# fpga23-serdes-power.net
KiCad netlist of a schematic drawn in Altium Designer
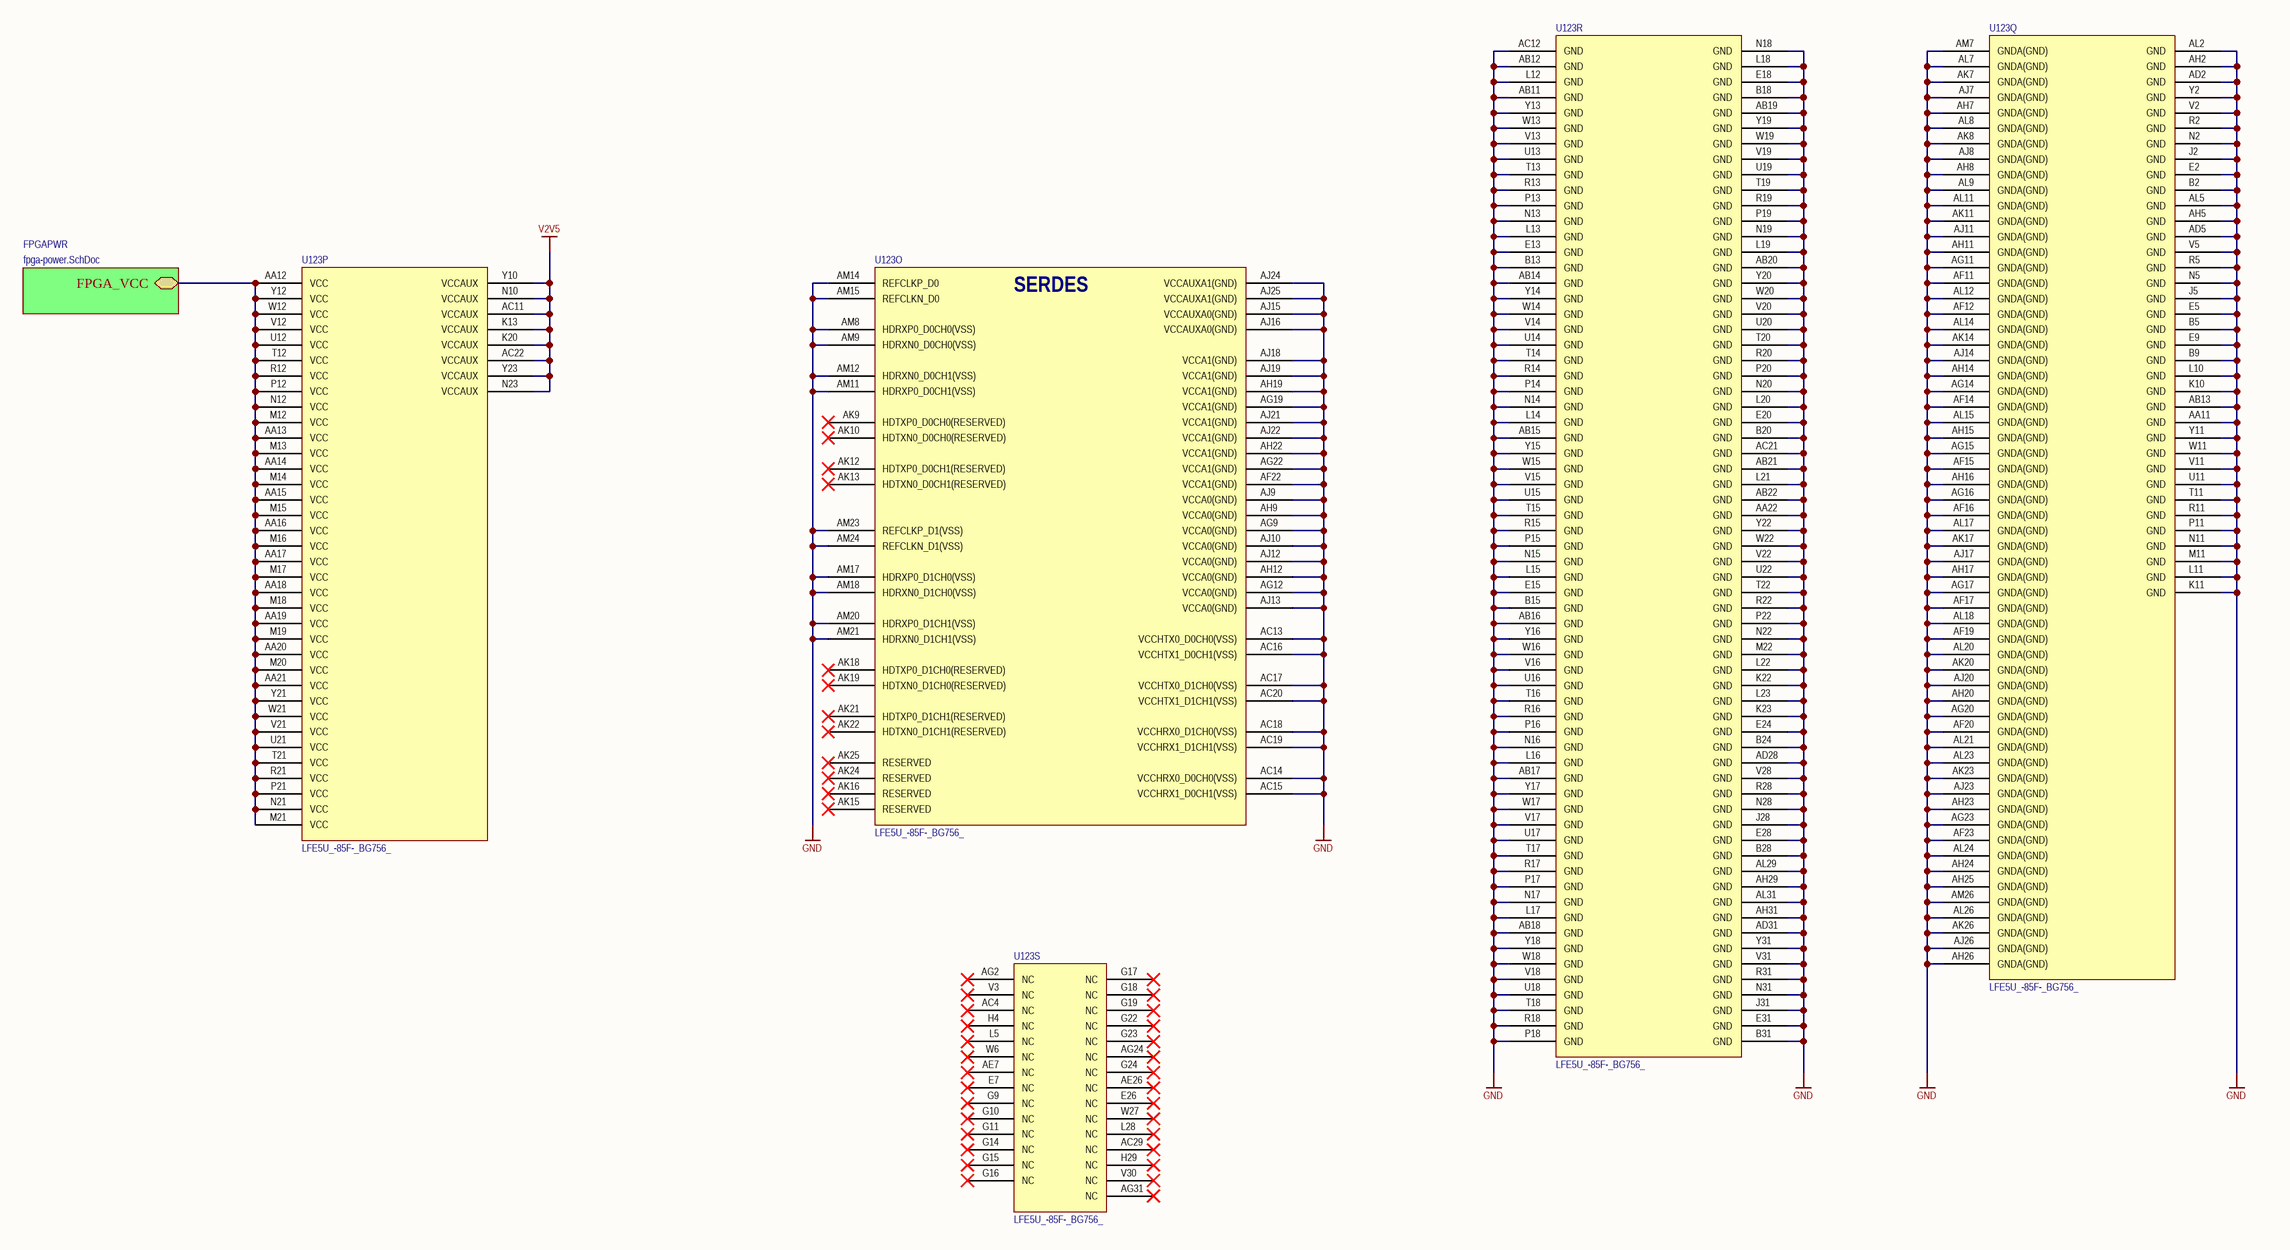
[diagram p0: fpga23-serdes-power.SchDoc]

(export (version "E")
  (design (tool "Eeschema 10.0.6"))
  (components
    (comp (ref "U123")
      (value "LFE5U_-85F-_BG756_")
      (footprint "lattice:caBGA756")
      (description "ECP5 FPGA, 85k LUT, 756-caBGA")
      (fields (field (name "MANUFACTURER") "Lattice Semiconductor"))
      (libsource (lib "lattice") (part "LFE5U_-85F-_BG756_"))
    )
  )
  (nets
    (net (code "1") (name "/FPGA_VCC") (class "Default")
      (node (ref "U123") (pin "AA12") (pinfunction "VCC_AA12") (pintype "power_in"))
      (node (ref "U123") (pin "AA13") (pinfunction "VCC_AA13") (pintype "power_in"))
      (node (ref "U123") (pin "AA14") (pinfunction "VCC_AA14") (pintype "power_in"))
      (node (ref "U123") (pin "AA15") (pinfunction "VCC_AA15") (pintype "power_in"))
      (node (ref "U123") (pin "AA16") (pinfunction "VCC_AA16") (pintype "power_in"))
      (node (ref "U123") (pin "AA17") (pinfunction "VCC_AA17") (pintype "power_in"))
      (node (ref "U123") (pin "AA18") (pinfunction "VCC_AA18") (pintype "power_in"))
      (node (ref "U123") (pin "AA19") (pinfunction "VCC_AA19") (pintype "power_in"))
      (node (ref "U123") (pin "AA20") (pinfunction "VCC_AA20") (pintype "power_in"))
      (node (ref "U123") (pin "AA21") (pinfunction "VCC_AA21") (pintype "power_in"))
      (node (ref "U123") (pin "M12") (pinfunction "VCC_M12") (pintype "power_in"))
      (node (ref "U123") (pin "M13") (pinfunction "VCC_M13") (pintype "power_in"))
      (node (ref "U123") (pin "M14") (pinfunction "VCC_M14") (pintype "power_in"))
      (node (ref "U123") (pin "M15") (pinfunction "VCC_M15") (pintype "power_in"))
      (node (ref "U123") (pin "M16") (pinfunction "VCC_M16") (pintype "power_in"))
      (node (ref "U123") (pin "M17") (pinfunction "VCC_M17") (pintype "power_in"))
      (node (ref "U123") (pin "M18") (pinfunction "VCC_M18") (pintype "power_in"))
      (node (ref "U123") (pin "M19") (pinfunction "VCC_M19") (pintype "power_in"))
      (node (ref "U123") (pin "M20") (pinfunction "VCC_M20") (pintype "power_in"))
      (node (ref "U123") (pin "M21") (pinfunction "VCC_M21") (pintype "power_in"))
      (node (ref "U123") (pin "N12") (pinfunction "VCC_N12") (pintype "power_in"))
      (node (ref "U123") (pin "N21") (pinfunction "VCC_N21") (pintype "power_in"))
      (node (ref "U123") (pin "P12") (pinfunction "VCC_P12") (pintype "power_in"))
      (node (ref "U123") (pin "P21") (pinfunction "VCC_P21") (pintype "power_in"))
      (node (ref "U123") (pin "R12") (pinfunction "VCC_R12") (pintype "power_in"))
      (node (ref "U123") (pin "R21") (pinfunction "VCC_R21") (pintype "power_in"))
      (node (ref "U123") (pin "T12") (pinfunction "VCC_T12") (pintype "power_in"))
      (node (ref "U123") (pin "T21") (pinfunction "VCC_T21") (pintype "power_in"))
      (node (ref "U123") (pin "U12") (pinfunction "VCC_U12") (pintype "power_in"))
      (node (ref "U123") (pin "U21") (pinfunction "VCC_U21") (pintype "power_in"))
      (node (ref "U123") (pin "V12") (pinfunction "VCC_V12") (pintype "power_in"))
      (node (ref "U123") (pin "V21") (pinfunction "VCC_V21") (pintype "power_in"))
      (node (ref "U123") (pin "W12") (pinfunction "VCC_W12") (pintype "power_in"))
      (node (ref "U123") (pin "W21") (pinfunction "VCC_W21") (pintype "power_in"))
      (node (ref "U123") (pin "Y12") (pinfunction "VCC_Y12") (pintype "power_in"))
      (node (ref "U123") (pin "Y21") (pinfunction "VCC_Y21") (pintype "power_in"))
    )
    (net (code "2") (name "GND") (class "Default")
      (node (ref "U123") (pin "AA11") (pinfunction "GND_AA11") (pintype "power_in"))
      (node (ref "U123") (pin "AA22") (pinfunction "GND_AA22") (pintype "power_in"))
      (node (ref "U123") (pin "AB11") (pinfunction "GND_AB11") (pintype "power_in"))
      (node (ref "U123") (pin "AB12") (pinfunction "GND_AB12") (pintype "power_in"))
      (node (ref "U123") (pin "AB13") (pinfunction "GND_AB13") (pintype "power_in"))
      (node (ref "U123") (pin "AB14") (pinfunction "GND_AB14") (pintype "power_in"))
      (node (ref "U123") (pin "AB15") (pinfunction "GND_AB15") (pintype "power_in"))
      (node (ref "U123") (pin "AB16") (pinfunction "GND_AB16") (pintype "power_in"))
      (node (ref "U123") (pin "AB17") (pinfunction "GND_AB17") (pintype "power_in"))
      (node (ref "U123") (pin "AB18") (pinfunction "GND_AB18") (pintype "power_in"))
      (node (ref "U123") (pin "AB19") (pinfunction "GND_AB19") (pintype "power_in"))
      (node (ref "U123") (pin "AB20") (pinfunction "GND_AB20") (pintype "power_in"))
      (node (ref "U123") (pin "AB21") (pinfunction "GND_AB21") (pintype "power_in"))
      (node (ref "U123") (pin "AB22") (pinfunction "GND_AB22") (pintype "power_in"))
      (node (ref "U123") (pin "AC12") (pinfunction "GND_AC12") (pintype "power_in"))
      (node (ref "U123") (pin "AC13") (pinfunction "VCCHTX0_D0CH0(VSS)_AC13") (pintype "power_in"))
      (node (ref "U123") (pin "AC14") (pinfunction "VCCHRX0_D0CH0(VSS)_AC14") (pintype "power_in"))
      (node (ref "U123") (pin "AC15") (pinfunction "VCCHRX1_D0CH1(VSS)_AC15") (pintype "power_in"))
      (node (ref "U123") (pin "AC16") (pinfunction "VCCHTX1_D0CH1(VSS)_AC16") (pintype "power_in"))
      (node (ref "U123") (pin "AC17") (pinfunction "VCCHTX0_D1CH0(VSS)_AC17") (pintype "power_in"))
      (node (ref "U123") (pin "AC18") (pinfunction "VCCHRX0_D1CH0(VSS)_AC18") (pintype "power_in"))
      (node (ref "U123") (pin "AC19") (pinfunction "VCCHRX1_D1CH1(VSS)_AC19") (pintype "power_in"))
      (node (ref "U123") (pin "AC20") (pinfunction "VCCHTX1_D1CH1(VSS)_AC20") (pintype "power_in"))
      (node (ref "U123") (pin "AC21") (pinfunction "GND_AC21") (pintype "power_in"))
      (node (ref "U123") (pin "AD2") (pinfunction "GND_AD2") (pintype "power_in"))
      (node (ref "U123") (pin "AD28") (pinfunction "GND_AD28") (pintype "power_in"))
      (node (ref "U123") (pin "AD31") (pinfunction "GND_AD31") (pintype "power_in"))
      (node (ref "U123") (pin "AD5") (pinfunction "GND_AD5") (pintype "power_in"))
      (node (ref "U123") (pin "AF11") (pinfunction "GNDA(GND)_AF11") (pintype "power_in"))
      (node (ref "U123") (pin "AF12") (pinfunction "GNDA(GND)_AF12") (pintype "power_in"))
      (node (ref "U123") (pin "AF14") (pinfunction "GNDA(GND)_AF14") (pintype "power_in"))
      (node (ref "U123") (pin "AF15") (pinfunction "GNDA(GND)_AF15") (pintype "power_in"))
      (node (ref "U123") (pin "AF16") (pinfunction "GNDA(GND)_AF16") (pintype "power_in"))
      (node (ref "U123") (pin "AF17") (pinfunction "GNDA(GND)_AF17") (pintype "power_in"))
      (node (ref "U123") (pin "AF19") (pinfunction "GNDA(GND)_AF19") (pintype "power_in"))
      (node (ref "U123") (pin "AF20") (pinfunction "GNDA(GND)_AF20") (pintype "power_in"))
      (node (ref "U123") (pin "AF22") (pinfunction "VCCA1(GND)_AF22") (pintype "power_in"))
      (node (ref "U123") (pin "AF23") (pinfunction "GNDA(GND)_AF23") (pintype "power_in"))
      (node (ref "U123") (pin "AG11") (pinfunction "GNDA(GND)_AG11") (pintype "power_in"))
      (node (ref "U123") (pin "AG12") (pinfunction "VCCA0(GND)_AG12") (pintype "power_in"))
      (node (ref "U123") (pin "AG14") (pinfunction "GNDA(GND)_AG14") (pintype "power_in"))
      (node (ref "U123") (pin "AG15") (pinfunction "GNDA(GND)_AG15") (pintype "power_in"))
      (node (ref "U123") (pin "AG16") (pinfunction "GNDA(GND)_AG16") (pintype "power_in"))
      (node (ref "U123") (pin "AG17") (pinfunction "GNDA(GND)_AG17") (pintype "power_in"))
      (node (ref "U123") (pin "AG19") (pinfunction "VCCA1(GND)_AG19") (pintype "power_in"))
      (node (ref "U123") (pin "AG20") (pinfunction "GNDA(GND)_AG20") (pintype "power_in"))
      (node (ref "U123") (pin "AG22") (pinfunction "VCCA1(GND)_AG22") (pintype "power_in"))
      (node (ref "U123") (pin "AG23") (pinfunction "GNDA(GND)_AG23") (pintype "power_in"))
      (node (ref "U123") (pin "AG9") (pinfunction "VCCA0(GND)_AG9") (pintype "power_in"))
      (node (ref "U123") (pin "AH11") (pinfunction "GNDA(GND)_AH11") (pintype "power_in"))
      (node (ref "U123") (pin "AH12") (pinfunction "VCCA0(GND)_AH12") (pintype "power_in"))
      (node (ref "U123") (pin "AH14") (pinfunction "GNDA(GND)_AH14") (pintype "power_in"))
      (node (ref "U123") (pin "AH15") (pinfunction "GNDA(GND)_AH15") (pintype "power_in"))
      (node (ref "U123") (pin "AH16") (pinfunction "GNDA(GND)_AH16") (pintype "power_in"))
      (node (ref "U123") (pin "AH17") (pinfunction "GNDA(GND)_AH17") (pintype "power_in"))
      (node (ref "U123") (pin "AH19") (pinfunction "VCCA1(GND)_AH19") (pintype "power_in"))
      (node (ref "U123") (pin "AH2") (pinfunction "GND_AH2") (pintype "power_in"))
      (node (ref "U123") (pin "AH20") (pinfunction "GNDA(GND)_AH20") (pintype "power_in"))
      (node (ref "U123") (pin "AH22") (pinfunction "VCCA1(GND)_AH22") (pintype "power_in"))
      (node (ref "U123") (pin "AH23") (pinfunction "GNDA(GND)_AH23") (pintype "power_in"))
      (node (ref "U123") (pin "AH24") (pinfunction "GNDA(GND)_AH24") (pintype "power_in"))
      (node (ref "U123") (pin "AH25") (pinfunction "GNDA(GND)_AH25") (pintype "power_in"))
      (node (ref "U123") (pin "AH26") (pinfunction "GNDA(GND)_AH26") (pintype "power_in"))
      (node (ref "U123") (pin "AH29") (pinfunction "GND_AH29") (pintype "power_in"))
      (node (ref "U123") (pin "AH31") (pinfunction "GND_AH31") (pintype "power_in"))
      (node (ref "U123") (pin "AH5") (pinfunction "GND_AH5") (pintype "power_in"))
      (node (ref "U123") (pin "AH7") (pinfunction "GNDA(GND)_AH7") (pintype "power_in"))
      (node (ref "U123") (pin "AH8") (pinfunction "GNDA(GND)_AH8") (pintype "power_in"))
      (node (ref "U123") (pin "AH9") (pinfunction "VCCA0(GND)_AH9") (pintype "power_in"))
      (node (ref "U123") (pin "AJ10") (pinfunction "VCCA0(GND)_AJ10") (pintype "power_in"))
      (node (ref "U123") (pin "AJ11") (pinfunction "GNDA(GND)_AJ11") (pintype "power_in"))
      (node (ref "U123") (pin "AJ12") (pinfunction "VCCA0(GND)_AJ12") (pintype "power_in"))
      (node (ref "U123") (pin "AJ13") (pinfunction "VCCA0(GND)_AJ13") (pintype "power_in"))
      (node (ref "U123") (pin "AJ14") (pinfunction "GNDA(GND)_AJ14") (pintype "power_in"))
      (node (ref "U123") (pin "AJ15") (pinfunction "VCCAUXA0(GND)_AJ15") (pintype "power_in"))
      (node (ref "U123") (pin "AJ16") (pinfunction "VCCAUXA0(GND)_AJ16") (pintype "power_in"))
      (node (ref "U123") (pin "AJ17") (pinfunction "GNDA(GND)_AJ17") (pintype "power_in"))
      (node (ref "U123") (pin "AJ18") (pinfunction "VCCA1(GND)_AJ18") (pintype "power_in"))
      (node (ref "U123") (pin "AJ19") (pinfunction "VCCA1(GND)_AJ19") (pintype "power_in"))
      (node (ref "U123") (pin "AJ20") (pinfunction "GNDA(GND)_AJ20") (pintype "power_in"))
      (node (ref "U123") (pin "AJ21") (pinfunction "VCCA1(GND)_AJ21") (pintype "power_in"))
      (node (ref "U123") (pin "AJ22") (pinfunction "VCCA1(GND)_AJ22") (pintype "power_in"))
      (node (ref "U123") (pin "AJ23") (pinfunction "GNDA(GND)_AJ23") (pintype "power_in"))
      (node (ref "U123") (pin "AJ24") (pinfunction "VCCAUXA1(GND)_AJ24") (pintype "power_in"))
      (node (ref "U123") (pin "AJ25") (pinfunction "VCCAUXA1(GND)_AJ25") (pintype "power_in"))
      (node (ref "U123") (pin "AJ26") (pinfunction "GNDA(GND)_AJ26") (pintype "power_in"))
      (node (ref "U123") (pin "AJ7") (pinfunction "GNDA(GND)_AJ7") (pintype "power_in"))
      (node (ref "U123") (pin "AJ8") (pinfunction "GNDA(GND)_AJ8") (pintype "power_in"))
      (node (ref "U123") (pin "AJ9") (pinfunction "VCCA0(GND)_AJ9") (pintype "power_in"))
      (node (ref "U123") (pin "AK11") (pinfunction "GNDA(GND)_AK11") (pintype "power_in"))
      (node (ref "U123") (pin "AK14") (pinfunction "GNDA(GND)_AK14") (pintype "power_in"))
      (node (ref "U123") (pin "AK17") (pinfunction "GNDA(GND)_AK17") (pintype "power_in"))
      (node (ref "U123") (pin "AK20") (pinfunction "GNDA(GND)_AK20") (pintype "power_in"))
      (node (ref "U123") (pin "AK23") (pinfunction "GNDA(GND)_AK23") (pintype "power_in"))
      (node (ref "U123") (pin "AK26") (pinfunction "GNDA(GND)_AK26") (pintype "power_in"))
      (node (ref "U123") (pin "AK7") (pinfunction "GNDA(GND)_AK7") (pintype "power_in"))
      (node (ref "U123") (pin "AK8") (pinfunction "GNDA(GND)_AK8") (pintype "power_in"))
      (node (ref "U123") (pin "AL11") (pinfunction "GNDA(GND)_AL11") (pintype "power_in"))
      (node (ref "U123") (pin "AL12") (pinfunction "GNDA(GND)_AL12") (pintype "power_in"))
      (node (ref "U123") (pin "AL14") (pinfunction "GNDA(GND)_AL14") (pintype "power_in"))
      (node (ref "U123") (pin "AL15") (pinfunction "GNDA(GND)_AL15") (pintype "power_in"))
      (node (ref "U123") (pin "AL17") (pinfunction "GNDA(GND)_AL17") (pintype "power_in"))
      (node (ref "U123") (pin "AL18") (pinfunction "GNDA(GND)_AL18") (pintype "power_in"))
      (node (ref "U123") (pin "AL2") (pinfunction "GND_AL2") (pintype "power_in"))
      (node (ref "U123") (pin "AL20") (pinfunction "GNDA(GND)_AL20") (pintype "power_in"))
      (node (ref "U123") (pin "AL21") (pinfunction "GNDA(GND)_AL21") (pintype "power_in"))
      (node (ref "U123") (pin "AL23") (pinfunction "GNDA(GND)_AL23") (pintype "power_in"))
      (node (ref "U123") (pin "AL24") (pinfunction "GNDA(GND)_AL24") (pintype "power_in"))
      (node (ref "U123") (pin "AL26") (pinfunction "GNDA(GND)_AL26") (pintype "power_in"))
      (node (ref "U123") (pin "AL29") (pinfunction "GND_AL29") (pintype "power_in"))
      (node (ref "U123") (pin "AL31") (pinfunction "GND_AL31") (pintype "power_in"))
      (node (ref "U123") (pin "AL5") (pinfunction "GND_AL5") (pintype "power_in"))
      (node (ref "U123") (pin "AL7") (pinfunction "GNDA(GND)_AL7") (pintype "power_in"))
      (node (ref "U123") (pin "AL8") (pinfunction "GNDA(GND)_AL8") (pintype "power_in"))
      (node (ref "U123") (pin "AL9") (pinfunction "GNDA(GND)_AL9") (pintype "power_in"))
      (node (ref "U123") (pin "AM11") (pinfunction "HDRXP0_D0CH1(VSS)_AM11") (pintype "passive"))
      (node (ref "U123") (pin "AM12") (pinfunction "HDRXN0_D0CH1(VSS)_AM12") (pintype "passive"))
      (node (ref "U123") (pin "AM14") (pinfunction "REFCLKP_D0_AM14") (pintype "passive"))
      (node (ref "U123") (pin "AM15") (pinfunction "REFCLKN_D0_AM15") (pintype "passive"))
      (node (ref "U123") (pin "AM17") (pinfunction "HDRXP0_D1CH0(VSS)_AM17") (pintype "passive"))
      (node (ref "U123") (pin "AM18") (pinfunction "HDRXN0_D1CH0(VSS)_AM18") (pintype "passive"))
      (node (ref "U123") (pin "AM20") (pinfunction "HDRXP0_D1CH1(VSS)_AM20") (pintype "passive"))
      (node (ref "U123") (pin "AM21") (pinfunction "HDRXN0_D1CH1(VSS)_AM21") (pintype "passive"))
      (node (ref "U123") (pin "AM23") (pinfunction "REFCLKP_D1(VSS)_AM23") (pintype "passive"))
      (node (ref "U123") (pin "AM24") (pinfunction "REFCLKN_D1(VSS)_AM24") (pintype "passive"))
      (node (ref "U123") (pin "AM26") (pinfunction "GNDA(GND)_AM26") (pintype "power_in"))
      (node (ref "U123") (pin "AM7") (pinfunction "GNDA(GND)_AM7") (pintype "power_in"))
      (node (ref "U123") (pin "AM8") (pinfunction "HDRXP0_D0CH0(VSS)_AM8") (pintype "passive"))
      (node (ref "U123") (pin "AM9") (pinfunction "HDRXN0_D0CH0(VSS)_AM9") (pintype "passive"))
      (node (ref "U123") (pin "B13") (pinfunction "GND_B13") (pintype "power_in"))
      (node (ref "U123") (pin "B15") (pinfunction "GND_B15") (pintype "power_in"))
      (node (ref "U123") (pin "B18") (pinfunction "GND_B18") (pintype "power_in"))
      (node (ref "U123") (pin "B2") (pinfunction "GND_B2") (pintype "power_in"))
      (node (ref "U123") (pin "B20") (pinfunction "GND_B20") (pintype "power_in"))
      (node (ref "U123") (pin "B24") (pinfunction "GND_B24") (pintype "power_in"))
      (node (ref "U123") (pin "B28") (pinfunction "GND_B28") (pintype "power_in"))
      (node (ref "U123") (pin "B31") (pinfunction "GND_B31") (pintype "power_in"))
      (node (ref "U123") (pin "B5") (pinfunction "GND_B5") (pintype "power_in"))
      (node (ref "U123") (pin "B9") (pinfunction "GND_B9") (pintype "power_in"))
      (node (ref "U123") (pin "E13") (pinfunction "GND_E13") (pintype "power_in"))
      (node (ref "U123") (pin "E15") (pinfunction "GND_E15") (pintype "power_in"))
      (node (ref "U123") (pin "E18") (pinfunction "GND_E18") (pintype "power_in"))
      (node (ref "U123") (pin "E2") (pinfunction "GND_E2") (pintype "power_in"))
      (node (ref "U123") (pin "E20") (pinfunction "GND_E20") (pintype "power_in"))
      (node (ref "U123") (pin "E24") (pinfunction "GND_E24") (pintype "power_in"))
      (node (ref "U123") (pin "E28") (pinfunction "GND_E28") (pintype "power_in"))
      (node (ref "U123") (pin "E31") (pinfunction "GND_E31") (pintype "power_in"))
      (node (ref "U123") (pin "E5") (pinfunction "GND_E5") (pintype "power_in"))
      (node (ref "U123") (pin "E9") (pinfunction "GND_E9") (pintype "power_in"))
      (node (ref "U123") (pin "J2") (pinfunction "GND_J2") (pintype "power_in"))
      (node (ref "U123") (pin "J28") (pinfunction "GND_J28") (pintype "power_in"))
      (node (ref "U123") (pin "J31") (pinfunction "GND_J31") (pintype "power_in"))
      (node (ref "U123") (pin "J5") (pinfunction "GND_J5") (pintype "power_in"))
      (node (ref "U123") (pin "K10") (pinfunction "GND_K10") (pintype "power_in"))
      (node (ref "U123") (pin "K11") (pinfunction "GND_K11") (pintype "power_in"))
      (node (ref "U123") (pin "K22") (pinfunction "GND_K22") (pintype "power_in"))
      (node (ref "U123") (pin "K23") (pinfunction "GND_K23") (pintype "power_in"))
      (node (ref "U123") (pin "L10") (pinfunction "GND_L10") (pintype "power_in"))
      (node (ref "U123") (pin "L11") (pinfunction "GND_L11") (pintype "power_in"))
      (node (ref "U123") (pin "L12") (pinfunction "GND_L12") (pintype "power_in"))
      (node (ref "U123") (pin "L13") (pinfunction "GND_L13") (pintype "power_in"))
      (node (ref "U123") (pin "L14") (pinfunction "GND_L14") (pintype "power_in"))
      (node (ref "U123") (pin "L15") (pinfunction "GND_L15") (pintype "power_in"))
      (node (ref "U123") (pin "L16") (pinfunction "GND_L16") (pintype "power_in"))
      (node (ref "U123") (pin "L17") (pinfunction "GND_L17") (pintype "power_in"))
      (node (ref "U123") (pin "L18") (pinfunction "GND_L18") (pintype "power_in"))
      (node (ref "U123") (pin "L19") (pinfunction "GND_L19") (pintype "power_in"))
      (node (ref "U123") (pin "L20") (pinfunction "GND_L20") (pintype "power_in"))
      (node (ref "U123") (pin "L21") (pinfunction "GND_L21") (pintype "power_in"))
      (node (ref "U123") (pin "L22") (pinfunction "GND_L22") (pintype "power_in"))
      (node (ref "U123") (pin "L23") (pinfunction "GND_L23") (pintype "power_in"))
      (node (ref "U123") (pin "M11") (pinfunction "GND_M11") (pintype "power_in"))
      (node (ref "U123") (pin "M22") (pinfunction "GND_M22") (pintype "power_in"))
      (node (ref "U123") (pin "N11") (pinfunction "GND_N11") (pintype "power_in"))
      (node (ref "U123") (pin "N13") (pinfunction "GND_N13") (pintype "power_in"))
      (node (ref "U123") (pin "N14") (pinfunction "GND_N14") (pintype "power_in"))
      (node (ref "U123") (pin "N15") (pinfunction "GND_N15") (pintype "power_in"))
      (node (ref "U123") (pin "N16") (pinfunction "GND_N16") (pintype "power_in"))
      (node (ref "U123") (pin "N17") (pinfunction "GND_N17") (pintype "power_in"))
      (node (ref "U123") (pin "N18") (pinfunction "GND_N18") (pintype "power_in"))
      (node (ref "U123") (pin "N19") (pinfunction "GND_N19") (pintype "power_in"))
      (node (ref "U123") (pin "N2") (pinfunction "GND_N2") (pintype "power_in"))
      (node (ref "U123") (pin "N20") (pinfunction "GND_N20") (pintype "power_in"))
      (node (ref "U123") (pin "N22") (pinfunction "GND_N22") (pintype "power_in"))
      (node (ref "U123") (pin "N28") (pinfunction "GND_N28") (pintype "power_in"))
      (node (ref "U123") (pin "N31") (pinfunction "GND_N31") (pintype "power_in"))
      (node (ref "U123") (pin "N5") (pinfunction "GND_N5") (pintype "power_in"))
      (node (ref "U123") (pin "P11") (pinfunction "GND_P11") (pintype "power_in"))
      (node (ref "U123") (pin "P13") (pinfunction "GND_P13") (pintype "power_in"))
      (node (ref "U123") (pin "P14") (pinfunction "GND_P14") (pintype "power_in"))
      (node (ref "U123") (pin "P15") (pinfunction "GND_P15") (pintype "power_in"))
      (node (ref "U123") (pin "P16") (pinfunction "GND_P16") (pintype "power_in"))
      (node (ref "U123") (pin "P17") (pinfunction "GND_P17") (pintype "power_in"))
      (node (ref "U123") (pin "P18") (pinfunction "GND_P18") (pintype "power_in"))
      (node (ref "U123") (pin "P19") (pinfunction "GND_P19") (pintype "power_in"))
      (node (ref "U123") (pin "P20") (pinfunction "GND_P20") (pintype "power_in"))
      (node (ref "U123") (pin "P22") (pinfunction "GND_P22") (pintype "power_in"))
      (node (ref "U123") (pin "R11") (pinfunction "GND_R11") (pintype "power_in"))
      (node (ref "U123") (pin "R13") (pinfunction "GND_R13") (pintype "power_in"))
      (node (ref "U123") (pin "R14") (pinfunction "GND_R14") (pintype "power_in"))
      (node (ref "U123") (pin "R15") (pinfunction "GND_R15") (pintype "power_in"))
      (node (ref "U123") (pin "R16") (pinfunction "GND_R16") (pintype "power_in"))
      (node (ref "U123") (pin "R17") (pinfunction "GND_R17") (pintype "power_in"))
      (node (ref "U123") (pin "R18") (pinfunction "GND_R18") (pintype "power_in"))
      (node (ref "U123") (pin "R19") (pinfunction "GND_R19") (pintype "power_in"))
      (node (ref "U123") (pin "R2") (pinfunction "GND_R2") (pintype "power_in"))
      (node (ref "U123") (pin "R20") (pinfunction "GND_R20") (pintype "power_in"))
      (node (ref "U123") (pin "R22") (pinfunction "GND_R22") (pintype "power_in"))
      (node (ref "U123") (pin "R28") (pinfunction "GND_R28") (pintype "power_in"))
      (node (ref "U123") (pin "R31") (pinfunction "GND_R31") (pintype "power_in"))
      (node (ref "U123") (pin "R5") (pinfunction "GND_R5") (pintype "power_in"))
      (node (ref "U123") (pin "T11") (pinfunction "GND_T11") (pintype "power_in"))
      (node (ref "U123") (pin "T13") (pinfunction "GND_T13") (pintype "power_in"))
      (node (ref "U123") (pin "T14") (pinfunction "GND_T14") (pintype "power_in"))
      (node (ref "U123") (pin "T15") (pinfunction "GND_T15") (pintype "power_in"))
      (node (ref "U123") (pin "T16") (pinfunction "GND_T16") (pintype "power_in"))
      (node (ref "U123") (pin "T17") (pinfunction "GND_T17") (pintype "power_in"))
      (node (ref "U123") (pin "T18") (pinfunction "GND_T18") (pintype "power_in"))
      (node (ref "U123") (pin "T19") (pinfunction "GND_T19") (pintype "power_in"))
      (node (ref "U123") (pin "T20") (pinfunction "GND_T20") (pintype "power_in"))
      (node (ref "U123") (pin "T22") (pinfunction "GND_T22") (pintype "power_in"))
      (node (ref "U123") (pin "U11") (pinfunction "GND_U11") (pintype "power_in"))
      (node (ref "U123") (pin "U13") (pinfunction "GND_U13") (pintype "power_in"))
      (node (ref "U123") (pin "U14") (pinfunction "GND_U14") (pintype "power_in"))
      (node (ref "U123") (pin "U15") (pinfunction "GND_U15") (pintype "power_in"))
      (node (ref "U123") (pin "U16") (pinfunction "GND_U16") (pintype "power_in"))
      (node (ref "U123") (pin "U17") (pinfunction "GND_U17") (pintype "power_in"))
      (node (ref "U123") (pin "U18") (pinfunction "GND_U18") (pintype "power_in"))
      (node (ref "U123") (pin "U19") (pinfunction "GND_U19") (pintype "power_in"))
      (node (ref "U123") (pin "U20") (pinfunction "GND_U20") (pintype "power_in"))
      (node (ref "U123") (pin "U22") (pinfunction "GND_U22") (pintype "power_in"))
      (node (ref "U123") (pin "V11") (pinfunction "GND_V11") (pintype "power_in"))
      (node (ref "U123") (pin "V13") (pinfunction "GND_V13") (pintype "power_in"))
      (node (ref "U123") (pin "V14") (pinfunction "GND_V14") (pintype "power_in"))
      (node (ref "U123") (pin "V15") (pinfunction "GND_V15") (pintype "power_in"))
      (node (ref "U123") (pin "V16") (pinfunction "GND_V16") (pintype "power_in"))
      (node (ref "U123") (pin "V17") (pinfunction "GND_V17") (pintype "power_in"))
      (node (ref "U123") (pin "V18") (pinfunction "GND_V18") (pintype "power_in"))
      (node (ref "U123") (pin "V19") (pinfunction "GND_V19") (pintype "power_in"))
      (node (ref "U123") (pin "V2") (pinfunction "GND_V2") (pintype "power_in"))
      (node (ref "U123") (pin "V20") (pinfunction "GND_V20") (pintype "power_in"))
      (node (ref "U123") (pin "V22") (pinfunction "GND_V22") (pintype "power_in"))
      (node (ref "U123") (pin "V28") (pinfunction "GND_V28") (pintype "power_in"))
      (node (ref "U123") (pin "V31") (pinfunction "GND_V31") (pintype "power_in"))
      (node (ref "U123") (pin "V5") (pinfunction "GND_V5") (pintype "power_in"))
      (node (ref "U123") (pin "W11") (pinfunction "GND_W11") (pintype "power_in"))
      (node (ref "U123") (pin "W13") (pinfunction "GND_W13") (pintype "power_in"))
      (node (ref "U123") (pin "W14") (pinfunction "GND_W14") (pintype "power_in"))
      (node (ref "U123") (pin "W15") (pinfunction "GND_W15") (pintype "power_in"))
      (node (ref "U123") (pin "W16") (pinfunction "GND_W16") (pintype "power_in"))
      (node (ref "U123") (pin "W17") (pinfunction "GND_W17") (pintype "power_in"))
      (node (ref "U123") (pin "W18") (pinfunction "GND_W18") (pintype "power_in"))
      (node (ref "U123") (pin "W19") (pinfunction "GND_W19") (pintype "power_in"))
      (node (ref "U123") (pin "W20") (pinfunction "GND_W20") (pintype "power_in"))
      (node (ref "U123") (pin "W22") (pinfunction "GND_W22") (pintype "power_in"))
      (node (ref "U123") (pin "Y11") (pinfunction "GND_Y11") (pintype "power_in"))
      (node (ref "U123") (pin "Y13") (pinfunction "GND_Y13") (pintype "power_in"))
      (node (ref "U123") (pin "Y14") (pinfunction "GND_Y14") (pintype "power_in"))
      (node (ref "U123") (pin "Y15") (pinfunction "GND_Y15") (pintype "power_in"))
      (node (ref "U123") (pin "Y16") (pinfunction "GND_Y16") (pintype "power_in"))
      (node (ref "U123") (pin "Y17") (pinfunction "GND_Y17") (pintype "power_in"))
      (node (ref "U123") (pin "Y18") (pinfunction "GND_Y18") (pintype "power_in"))
      (node (ref "U123") (pin "Y19") (pinfunction "GND_Y19") (pintype "power_in"))
      (node (ref "U123") (pin "Y2") (pinfunction "GND_Y2") (pintype "power_in"))
      (node (ref "U123") (pin "Y20") (pinfunction "GND_Y20") (pintype "power_in"))
      (node (ref "U123") (pin "Y22") (pinfunction "GND_Y22") (pintype "power_in"))
      (node (ref "U123") (pin "Y31") (pinfunction "GND_Y31") (pintype "power_in"))
    )
    (net (code "3") (name "V2V5") (class "Default")
      (node (ref "U123") (pin "AC11") (pinfunction "VCCAUX_AC11") (pintype "power_in"))
      (node (ref "U123") (pin "AC22") (pinfunction "VCCAUX_AC22") (pintype "power_in"))
      (node (ref "U123") (pin "K13") (pinfunction "VCCAUX_K13") (pintype "power_in"))
      (node (ref "U123") (pin "K20") (pinfunction "VCCAUX_K20") (pintype "power_in"))
      (node (ref "U123") (pin "N10") (pinfunction "VCCAUX_N10") (pintype "power_in"))
      (node (ref "U123") (pin "N23") (pinfunction "VCCAUX_N23") (pintype "power_in"))
      (node (ref "U123") (pin "Y10") (pinfunction "VCCAUX_Y10") (pintype "power_in"))
      (node (ref "U123") (pin "Y23") (pinfunction "VCCAUX_Y23") (pintype "power_in"))
    )
    (net (code "4") (name "unconnected-(U123O-HDTXN0_D0CH0(RESERVED)-PadAK10)") (class "Default")
      (node (ref "U123") (pin "AK10") (pinfunction "HDTXN0_D0CH0(RESERVED)_AK10") (pintype "passive+no_connect"))
    )
    (net (code "5") (name "unconnected-(U123O-HDTXN0_D0CH1(RESERVED)-PadAK13)") (class "Default")
      (node (ref "U123") (pin "AK13") (pinfunction "HDTXN0_D0CH1(RESERVED)_AK13") (pintype "passive+no_connect"))
    )
    (net (code "6") (name "unconnected-(U123O-HDTXN0_D1CH0(RESERVED)-PadAK19)") (class "Default")
      (node (ref "U123") (pin "AK19") (pinfunction "HDTXN0_D1CH0(RESERVED)_AK19") (pintype "passive+no_connect"))
    )
    (net (code "7") (name "unconnected-(U123O-HDTXN0_D1CH1(RESERVED)-PadAK22)") (class "Default")
      (node (ref "U123") (pin "AK22") (pinfunction "HDTXN0_D1CH1(RESERVED)_AK22") (pintype "passive+no_connect"))
    )
    (net (code "8") (name "unconnected-(U123O-HDTXP0_D0CH0(RESERVED)-PadAK9)") (class "Default")
      (node (ref "U123") (pin "AK9") (pinfunction "HDTXP0_D0CH0(RESERVED)_AK9") (pintype "passive+no_connect"))
    )
    (net (code "9") (name "unconnected-(U123O-HDTXP0_D0CH1(RESERVED)-PadAK12)") (class "Default")
      (node (ref "U123") (pin "AK12") (pinfunction "HDTXP0_D0CH1(RESERVED)_AK12") (pintype "passive+no_connect"))
    )
    (net (code "10") (name "unconnected-(U123O-HDTXP0_D1CH0(RESERVED)-PadAK18)") (class "Default")
      (node (ref "U123") (pin "AK18") (pinfunction "HDTXP0_D1CH0(RESERVED)_AK18") (pintype "passive+no_connect"))
    )
    (net (code "11") (name "unconnected-(U123O-HDTXP0_D1CH1(RESERVED)-PadAK21)") (class "Default")
      (node (ref "U123") (pin "AK21") (pinfunction "HDTXP0_D1CH1(RESERVED)_AK21") (pintype "passive+no_connect"))
    )
    (net (code "12") (name "unconnected-(U123O-RESERVED-PadAK15)") (class "Default")
      (node (ref "U123") (pin "AK15") (pinfunction "RESERVED_AK15") (pintype "passive+no_connect"))
    )
    (net (code "13") (name "unconnected-(U123O-RESERVED-PadAK16)") (class "Default")
      (node (ref "U123") (pin "AK16") (pinfunction "RESERVED_AK16") (pintype "passive+no_connect"))
    )
    (net (code "14") (name "unconnected-(U123O-RESERVED-PadAK24)") (class "Default")
      (node (ref "U123") (pin "AK24") (pinfunction "RESERVED_AK24") (pintype "passive+no_connect"))
    )
    (net (code "15") (name "unconnected-(U123O-RESERVED-PadAK25)") (class "Default")
      (node (ref "U123") (pin "AK25") (pinfunction "RESERVED_AK25") (pintype "passive+no_connect"))
    )
    (net (code "16") (name "unconnected-(U123S-NC-PadAC4)") (class "Default")
      (node (ref "U123") (pin "AC4") (pinfunction "NC_AC4") (pintype "passive+no_connect"))
    )
    (net (code "17") (name "unconnected-(U123S-NC-PadAC29)") (class "Default")
      (node (ref "U123") (pin "AC29") (pinfunction "NC_AC29") (pintype "passive+no_connect"))
    )
    (net (code "18") (name "unconnected-(U123S-NC-PadAE7)") (class "Default")
      (node (ref "U123") (pin "AE7") (pinfunction "NC_AE7") (pintype "passive+no_connect"))
    )
    (net (code "19") (name "unconnected-(U123S-NC-PadAE26)") (class "Default")
      (node (ref "U123") (pin "AE26") (pinfunction "NC_AE26") (pintype "passive+no_connect"))
    )
    (net (code "20") (name "unconnected-(U123S-NC-PadAG2)") (class "Default")
      (node (ref "U123") (pin "AG2") (pinfunction "NC_AG2") (pintype "passive+no_connect"))
    )
    (net (code "21") (name "unconnected-(U123S-NC-PadAG24)") (class "Default")
      (node (ref "U123") (pin "AG24") (pinfunction "NC_AG24") (pintype "passive+no_connect"))
    )
    (net (code "22") (name "unconnected-(U123S-NC-PadAG31)") (class "Default")
      (node (ref "U123") (pin "AG31") (pinfunction "NC_AG31") (pintype "passive+no_connect"))
    )
    (net (code "23") (name "unconnected-(U123S-NC-PadE7)") (class "Default")
      (node (ref "U123") (pin "E7") (pinfunction "NC_E7") (pintype "passive+no_connect"))
    )
    (net (code "24") (name "unconnected-(U123S-NC-PadE26)") (class "Default")
      (node (ref "U123") (pin "E26") (pinfunction "NC_E26") (pintype "passive+no_connect"))
    )
    (net (code "25") (name "unconnected-(U123S-NC-PadG9)") (class "Default")
      (node (ref "U123") (pin "G9") (pinfunction "NC_G9") (pintype "passive+no_connect"))
    )
    (net (code "26") (name "unconnected-(U123S-NC-PadG10)") (class "Default")
      (node (ref "U123") (pin "G10") (pinfunction "NC_G10") (pintype "passive+no_connect"))
    )
    (net (code "27") (name "unconnected-(U123S-NC-PadG11)") (class "Default")
      (node (ref "U123") (pin "G11") (pinfunction "NC_G11") (pintype "passive+no_connect"))
    )
    (net (code "28") (name "unconnected-(U123S-NC-PadG14)") (class "Default")
      (node (ref "U123") (pin "G14") (pinfunction "NC_G14") (pintype "passive+no_connect"))
    )
    (net (code "29") (name "unconnected-(U123S-NC-PadG15)") (class "Default")
      (node (ref "U123") (pin "G15") (pinfunction "NC_G15") (pintype "passive+no_connect"))
    )
    (net (code "30") (name "unconnected-(U123S-NC-PadG16)") (class "Default")
      (node (ref "U123") (pin "G16") (pinfunction "NC_G16") (pintype "passive+no_connect"))
    )
    (net (code "31") (name "unconnected-(U123S-NC-PadG17)") (class "Default")
      (node (ref "U123") (pin "G17") (pinfunction "NC_G17") (pintype "passive+no_connect"))
    )
    (net (code "32") (name "unconnected-(U123S-NC-PadG18)") (class "Default")
      (node (ref "U123") (pin "G18") (pinfunction "NC_G18") (pintype "passive+no_connect"))
    )
    (net (code "33") (name "unconnected-(U123S-NC-PadG19)") (class "Default")
      (node (ref "U123") (pin "G19") (pinfunction "NC_G19") (pintype "passive+no_connect"))
    )
    (net (code "34") (name "unconnected-(U123S-NC-PadG22)") (class "Default")
      (node (ref "U123") (pin "G22") (pinfunction "NC_G22") (pintype "passive+no_connect"))
    )
    (net (code "35") (name "unconnected-(U123S-NC-PadG23)") (class "Default")
      (node (ref "U123") (pin "G23") (pinfunction "NC_G23") (pintype "passive+no_connect"))
    )
    (net (code "36") (name "unconnected-(U123S-NC-PadG24)") (class "Default")
      (node (ref "U123") (pin "G24") (pinfunction "NC_G24") (pintype "passive+no_connect"))
    )
    (net (code "37") (name "unconnected-(U123S-NC-PadH4)") (class "Default")
      (node (ref "U123") (pin "H4") (pinfunction "NC_H4") (pintype "passive+no_connect"))
    )
    (net (code "38") (name "unconnected-(U123S-NC-PadH29)") (class "Default")
      (node (ref "U123") (pin "H29") (pinfunction "NC_H29") (pintype "passive+no_connect"))
    )
    (net (code "39") (name "unconnected-(U123S-NC-PadL5)") (class "Default")
      (node (ref "U123") (pin "L5") (pinfunction "NC_L5") (pintype "passive+no_connect"))
    )
    (net (code "40") (name "unconnected-(U123S-NC-PadL28)") (class "Default")
      (node (ref "U123") (pin "L28") (pinfunction "NC_L28") (pintype "passive+no_connect"))
    )
    (net (code "41") (name "unconnected-(U123S-NC-PadV3)") (class "Default")
      (node (ref "U123") (pin "V3") (pinfunction "NC_V3") (pintype "passive+no_connect"))
    )
    (net (code "42") (name "unconnected-(U123S-NC-PadV30)") (class "Default")
      (node (ref "U123") (pin "V30") (pinfunction "NC_V30") (pintype "passive+no_connect"))
    )
    (net (code "43") (name "unconnected-(U123S-NC-PadW6)") (class "Default")
      (node (ref "U123") (pin "W6") (pinfunction "NC_W6") (pintype "passive+no_connect"))
    )
    (net (code "44") (name "unconnected-(U123S-NC-PadW27)") (class "Default")
      (node (ref "U123") (pin "W27") (pinfunction "NC_W27") (pintype "passive+no_connect"))
    )
  )
)
